# Mach-rasp.net
KiCad netlist of a schematic drawn in Altium Designer
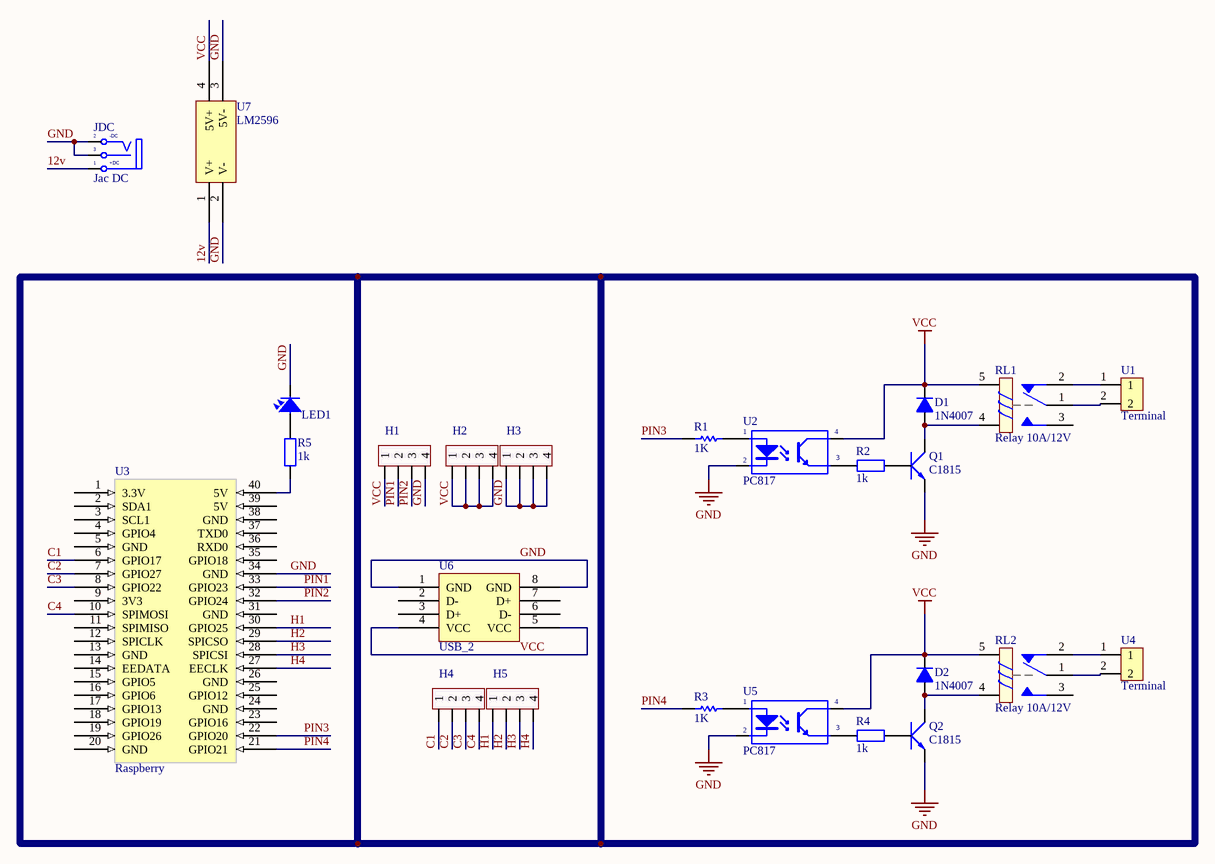
[diagram p0: Mach-rasp.SchDoc]

(export (version "E")
  (design (tool "Eeschema 10.0.6"))
  (components
    (comp (ref "D1")
      (value "1N4007")
      (footprint "D1A")
      (description "Diode 1A")
      (libsource (lib "syhaunguyen") (part "D1A"))
    )
    (comp (ref "D2")
      (value "1N4007")
      (footprint "D1A")
      (description "Diode 1A")
      (libsource (lib "syhaunguyen") (part "D1A"))
    )
    (comp (ref "H1")
      (value "Header4")
      (footprint "Header4")
      (description "Header IDC, 4 x 1 Pin Vertical 2.54mm Pitch (Non-Boxed, Male)")
      (libsource (lib "LIBRARY") (part "Header4"))
    )
    (comp (ref "H2")
      (value "Header4")
      (footprint "Header4")
      (description "Header IDC, 4 x 1 Pin Vertical 2.54mm Pitch (Non-Boxed, Male)")
      (libsource (lib "LIBRARY") (part "Header4"))
    )
    (comp (ref "H3")
      (value "Header4")
      (footprint "Header4")
      (description "Header IDC, 4 x 1 Pin Vertical 2.54mm Pitch (Non-Boxed, Male)")
      (libsource (lib "LIBRARY") (part "Header4"))
    )
    (comp (ref "H4")
      (value "Header4")
      (footprint "Header4")
      (description "Header IDC, 4 x 1 Pin Vertical 2.54mm Pitch (Non-Boxed, Male)")
      (libsource (lib "LIBRARY") (part "Header4"))
    )
    (comp (ref "H5")
      (value "Header4")
      (footprint "Header4")
      (description "Header IDC, 4 x 1 Pin Vertical 2.54mm Pitch (Non-Boxed, Male)")
      (libsource (lib "LIBRARY") (part "Header4"))
    )
    (comp (ref "JDC")
      (value "Jac DC")
      (footprint "DC-IN")
      (description "Jac DC input")
      (libsource (lib "syhaunguyen") (part "DCIN"))
    )
    (comp (ref "LED1")
      (value "LED")
      (footprint "LED-3")
      (description "LED Single colour Green and Red")
      (libsource (lib "syhaunguyen") (part "LED"))
    )
    (comp (ref "Q1")
      (value "C1815")
      (footprint "QTO-92")
      (description "NPN 600mW, ECB")
      (libsource (lib "syhaunguyen") (part "C1815"))
    )
    (comp (ref "Q2")
      (value "C1815")
      (footprint "QTO-92")
      (description "NPN 600mW, ECB")
      (libsource (lib "syhaunguyen") (part "C1815"))
    )
    (comp (ref "R1")
      (value "1K")
      (footprint "R1/4W")
      (description "Resistor")
      (fields
        (field (name "MANUFACTURER") "Generic Components")
        (field (name "Comment") "Res1")
        (field (name "PUBLISHER") "Altium Hobart Technology Centre")
      )
      (libsource (lib "syhaunguyen") (part "Res1_4"))
    )
    (comp (ref "R2")
      (value "1k")
      (footprint "R1/4W")
      (description "Resistor 1/4W")
      (libsource (lib "syhaunguyen") (part "R1/4W"))
    )
    (comp (ref "R3")
      (value "1K")
      (footprint "R1/4W")
      (description "Resistor")
      (fields
        (field (name "MANUFACTURER") "Generic Components")
        (field (name "Comment") "Res1")
        (field (name "PUBLISHER") "Altium Hobart Technology Centre")
      )
      (libsource (lib "syhaunguyen") (part "Res1_4"))
    )
    (comp (ref "R4")
      (value "1k")
      (footprint "R1/4W")
      (description "Resistor 1/4W")
      (libsource (lib "syhaunguyen") (part "R1/4W"))
    )
    (comp (ref "R5")
      (value "1k")
      (footprint "R1/4W")
      (description "Resistor 1/4W")
      (libsource (lib "syhaunguyen") (part "R1/4W"))
    )
    (comp (ref "RL1")
      (value "Relay 10A/12V")
      (footprint "RL_SPDT_10A")
      (description "Relay SPDT,10A - 12VDC 5 Pin")
      (libsource (lib "syhaunguyen") (part "Relay 1"))
    )
    (comp (ref "RL2")
      (value "Relay 10A/12V")
      (footprint "RL_SPDT_10A")
      (description "Relay SPDT,10A - 12VDC 5 Pin")
      (libsource (lib "syhaunguyen") (part "Relay 1"))
    )
    (comp (ref "U1")
      (value "Terminal")
      (footprint "Terminal 5.08")
      (libsource (lib "THU_VIEN_PQB_Schlib1") (part "TERMINAL5.08"))
    )
    (comp (ref "U2")
      (value "PC817")
      (footprint "DIP4/W0.3")
      (description "Single Opto")
      (libsource (lib "syhaunguyen") (part "PC817"))
    )
    (comp (ref "U3")
      (value "Raspberry")
      (footprint "Raspberry")
      (libsource (lib "THU_VIEN_PQB_Schlib1") (part "Raspberry"))
    )
    (comp (ref "U4")
      (value "Terminal")
      (footprint "Terminal 5.08")
      (libsource (lib "THU_VIEN_PQB_Schlib1") (part "TERMINAL5.08"))
    )
    (comp (ref "U5")
      (value "PC817")
      (footprint "DIP4/W0.3")
      (description "Single Opto")
      (libsource (lib "syhaunguyen") (part "PC817"))
    )
    (comp (ref "U6")
      (value "USB_2")
      (footprint "USB_2")
      (description "USB")
      (libsource (lib "THU_VIEN_PQB_Schlib1") (part "USB_2"))
    )
    (comp (ref "U7")
      (value "LM2596")
      (footprint "LM2596")
      (libsource (lib "THU_VIEN_PQB_Schlib1") (part "LM2596"))
    )
  )
  (nets
    (net (code "1") (name "/12v") (class "Default")
      (node (ref "JDC") (pin "1") (pinfunction "T_1") (pintype "passive"))
      (node (ref "U7") (pin "1") (pinfunction "V+_1") (pintype "power_in"))
    )
    (net (code "2") (name "/C1") (class "Default")
      (node (ref "H4") (pin "1") (pinfunction "1_1") (pintype "passive"))
      (node (ref "U3") (pin "6") (pinfunction "GPIO17_6") (pintype "input"))
    )
    (net (code "3") (name "/C2") (class "Default")
      (node (ref "H4") (pin "2") (pinfunction "2_2") (pintype "passive"))
      (node (ref "U3") (pin "7") (pinfunction "GPIO27_7") (pintype "input"))
    )
    (net (code "4") (name "/C3") (class "Default")
      (node (ref "H4") (pin "3") (pinfunction "3_3") (pintype "passive"))
      (node (ref "U3") (pin "8") (pinfunction "GPIO22_8") (pintype "input"))
    )
    (net (code "5") (name "/C4") (class "Default")
      (node (ref "H4") (pin "4") (pinfunction "4_4") (pintype "passive"))
      (node (ref "U3") (pin "10") (pinfunction "SPIMOSI_10") (pintype "input"))
    )
    (net (code "6") (name "/H1") (class "Default")
      (node (ref "H5") (pin "1") (pinfunction "1_1") (pintype "passive"))
      (node (ref "U3") (pin "30") (pinfunction "GPIO25_30") (pintype "input"))
    )
    (net (code "7") (name "/H2") (class "Default")
      (node (ref "H5") (pin "2") (pinfunction "2_2") (pintype "passive"))
      (node (ref "U3") (pin "29") (pinfunction "SPICSO_29") (pintype "input"))
    )
    (net (code "8") (name "/H3") (class "Default")
      (node (ref "H5") (pin "3") (pinfunction "3_3") (pintype "passive"))
      (node (ref "U3") (pin "28") (pinfunction "SPICSI_28") (pintype "input"))
    )
    (net (code "9") (name "/H4") (class "Default")
      (node (ref "H5") (pin "4") (pinfunction "4_4") (pintype "passive"))
      (node (ref "U3") (pin "27") (pinfunction "EECLK_27") (pintype "input"))
    )
    (net (code "10") (name "/PIN1") (class "Default")
      (node (ref "H1") (pin "2") (pinfunction "2_2") (pintype "passive"))
      (node (ref "U3") (pin "33") (pinfunction "GPIO23_33") (pintype "input"))
    )
    (net (code "11") (name "/PIN2") (class "Default")
      (node (ref "H1") (pin "3") (pinfunction "3_3") (pintype "passive"))
      (node (ref "U3") (pin "32") (pinfunction "GPIO24_32") (pintype "input"))
    )
    (net (code "12") (name "/PIN3") (class "Default")
      (node (ref "R1") (pin "2") (pinfunction "2_2") (pintype "passive"))
      (node (ref "U3") (pin "22") (pinfunction "GPIO20_22") (pintype "input"))
    )
    (net (code "13") (name "/PIN4") (class "Default")
      (node (ref "R3") (pin "2") (pinfunction "2_2") (pintype "passive"))
      (node (ref "U3") (pin "21") (pinfunction "GPIO21_21") (pintype "input"))
    )
    (net (code "14") (name "GND") (class "Default")
      (node (ref "H1") (pin "4") (pinfunction "4_4") (pintype "passive"))
      (node (ref "H3") (pin "1") (pinfunction "1_1") (pintype "passive"))
      (node (ref "H3") (pin "2") (pinfunction "2_2") (pintype "passive"))
      (node (ref "H3") (pin "3") (pinfunction "3_3") (pintype "passive"))
      (node (ref "H3") (pin "4") (pinfunction "4_4") (pintype "passive"))
      (node (ref "JDC") (pin "2") (pinfunction "TN_2") (pintype "passive"))
      (node (ref "JDC") (pin "3") (pinfunction "S_3") (pintype "power_in"))
      (node (ref "LED1") (pin "2") (pinfunction "2_2") (pintype "passive"))
      (node (ref "Q1") (pin "1") (pinfunction "E_1") (pintype "passive"))
      (node (ref "Q2") (pin "1") (pinfunction "E_1") (pintype "passive"))
      (node (ref "U2") (pin "2") (pinfunction "K_2") (pintype "passive"))
      (node (ref "U3") (pin "34") (pinfunction "GND_34") (pintype "input"))
      (node (ref "U5") (pin "2") (pinfunction "K_2") (pintype "passive"))
      (node (ref "U6") (pin "1") (pinfunction "GND_1") (pintype "passive"))
      (node (ref "U6") (pin "8") (pinfunction "GND_8") (pintype "passive"))
      (node (ref "U7") (pin "2") (pinfunction "V-_2") (pintype "power_in"))
      (node (ref "U7") (pin "3") (pinfunction "5V-_3") (pintype "power_in"))
    )
    (net (code "15") (name "Net-(D1-A)") (class "Default")
      (node (ref "D1") (pin "1") (pinfunction "A_1") (pintype "passive"))
      (node (ref "Q1") (pin "2") (pinfunction "C_2") (pintype "passive"))
      (node (ref "RL1") (pin "4") (pinfunction "4_4") (pintype "passive"))
    )
    (net (code "16") (name "Net-(D2-A)") (class "Default")
      (node (ref "D2") (pin "1") (pinfunction "A_1") (pintype "passive"))
      (node (ref "Q2") (pin "2") (pinfunction "C_2") (pintype "passive"))
      (node (ref "RL2") (pin "4") (pinfunction "4_4") (pintype "passive"))
    )
    (net (code "17") (name "Net-(LED1-Pad1)") (class "Default")
      (node (ref "LED1") (pin "1") (pinfunction "1_1") (pintype "passive"))
      (node (ref "R5") (pin "2") (pinfunction "2_2") (pintype "passive"))
    )
    (net (code "18") (name "Net-(Q1-B)") (class "Default")
      (node (ref "Q1") (pin "3") (pinfunction "B_3") (pintype "passive"))
      (node (ref "R2") (pin "2") (pinfunction "2_2") (pintype "passive"))
    )
    (net (code "19") (name "Net-(Q2-B)") (class "Default")
      (node (ref "Q2") (pin "3") (pinfunction "B_3") (pintype "passive"))
      (node (ref "R4") (pin "2") (pinfunction "2_2") (pintype "passive"))
    )
    (net (code "20") (name "Net-(R5-Pad1)") (class "Default")
      (node (ref "R5") (pin "1") (pinfunction "1_1") (pintype "passive"))
      (node (ref "U3") (pin "40") (pinfunction "5V_40") (pintype "input"))
    )
    (net (code "21") (name "Net-(RL1-Pad1)") (class "Default")
      (node (ref "RL1") (pin "1") (pinfunction "1_1") (pintype "passive"))
      (node (ref "U1") (pin "2") (pinfunction "2_2") (pintype "passive"))
    )
    (net (code "22") (name "Net-(RL1-Pad2)") (class "Default")
      (node (ref "RL1") (pin "2") (pinfunction "2_2") (pintype "passive"))
      (node (ref "U1") (pin "1") (pinfunction "1_1") (pintype "passive"))
    )
    (net (code "23") (name "Net-(RL2-Pad1)") (class "Default")
      (node (ref "RL2") (pin "1") (pinfunction "1_1") (pintype "passive"))
      (node (ref "U4") (pin "2") (pinfunction "2_2") (pintype "passive"))
    )
    (net (code "24") (name "Net-(RL2-Pad2)") (class "Default")
      (node (ref "RL2") (pin "2") (pinfunction "2_2") (pintype "passive"))
      (node (ref "U4") (pin "1") (pinfunction "1_1") (pintype "passive"))
    )
    (net (code "25") (name "Net-(U2-A)") (class "Default")
      (node (ref "R1") (pin "1") (pinfunction "1_1") (pintype "passive"))
      (node (ref "U2") (pin "1") (pinfunction "A_1") (pintype "passive"))
    )
    (net (code "26") (name "Net-(U2-E)") (class "Default")
      (node (ref "R2") (pin "1") (pinfunction "1_1") (pintype "passive"))
      (node (ref "U2") (pin "3") (pinfunction "E_3") (pintype "passive"))
    )
    (net (code "27") (name "Net-(U5-A)") (class "Default")
      (node (ref "R3") (pin "1") (pinfunction "1_1") (pintype "passive"))
      (node (ref "U5") (pin "1") (pinfunction "A_1") (pintype "passive"))
    )
    (net (code "28") (name "Net-(U5-E)") (class "Default")
      (node (ref "R4") (pin "1") (pinfunction "1_1") (pintype "passive"))
      (node (ref "U5") (pin "3") (pinfunction "E_3") (pintype "passive"))
    )
    (net (code "29") (name "VCC") (class "Default")
      (node (ref "D1") (pin "2") (pinfunction "K_2") (pintype "passive"))
      (node (ref "D2") (pin "2") (pinfunction "K_2") (pintype "passive"))
      (node (ref "H1") (pin "1") (pinfunction "1_1") (pintype "passive"))
      (node (ref "H2") (pin "1") (pinfunction "1_1") (pintype "passive"))
      (node (ref "H2") (pin "2") (pinfunction "2_2") (pintype "passive"))
      (node (ref "H2") (pin "3") (pinfunction "3_3") (pintype "passive"))
      (node (ref "H2") (pin "4") (pinfunction "4_4") (pintype "passive"))
      (node (ref "RL1") (pin "5") (pinfunction "5_5") (pintype "passive"))
      (node (ref "RL2") (pin "5") (pinfunction "5_5") (pintype "passive"))
      (node (ref "U2") (pin "4") (pinfunction "C_4") (pintype "passive"))
      (node (ref "U5") (pin "4") (pinfunction "C_4") (pintype "passive"))
      (node (ref "U6") (pin "4") (pinfunction "VCC_4") (pintype "passive"))
      (node (ref "U6") (pin "5") (pinfunction "VCC_5") (pintype "passive"))
      (node (ref "U7") (pin "4") (pinfunction "5V+_4") (pintype "power_in"))
    )
    (net (code "30") (name "unconnected-(RL1-Pad3)") (class "Default")
      (node (ref "RL1") (pin "3") (pinfunction "3_3") (pintype "passive"))
    )
    (net (code "31") (name "unconnected-(RL2-Pad3)") (class "Default")
      (node (ref "RL2") (pin "3") (pinfunction "3_3") (pintype "passive"))
    )
    (net (code "32") (name "unconnected-(U3-3.3V-Pad1)") (class "Default")
      (node (ref "U3") (pin "1") (pinfunction "3.3V_1") (pintype "input"))
    )
    (net (code "33") (name "unconnected-(U3-3V3-Pad9)") (class "Default")
      (node (ref "U3") (pin "9") (pinfunction "3V3_9") (pintype "input"))
    )
    (net (code "34") (name "unconnected-(U3-5V-Pad39)") (class "Default")
      (node (ref "U3") (pin "39") (pinfunction "5V_39") (pintype "input"))
    )
    (net (code "35") (name "unconnected-(U3-EEDATA-Pad14)") (class "Default")
      (node (ref "U3") (pin "14") (pinfunction "EEDATA_14") (pintype "input"))
    )
    (net (code "36") (name "unconnected-(U3-GND-Pad5)") (class "Default")
      (node (ref "U3") (pin "5") (pinfunction "GND_5") (pintype "input"))
    )
    (net (code "37") (name "unconnected-(U3-GND-Pad13)") (class "Default")
      (node (ref "U3") (pin "13") (pinfunction "GND_13") (pintype "input"))
    )
    (net (code "38") (name "unconnected-(U3-GND-Pad20)") (class "Default")
      (node (ref "U3") (pin "20") (pinfunction "GND_20") (pintype "input"))
    )
    (net (code "39") (name "unconnected-(U3-GND-Pad24)") (class "Default")
      (node (ref "U3") (pin "24") (pinfunction "GND_24") (pintype "input"))
    )
    (net (code "40") (name "unconnected-(U3-GND-Pad26)") (class "Default")
      (node (ref "U3") (pin "26") (pinfunction "GND_26") (pintype "input"))
    )
    (net (code "41") (name "unconnected-(U3-GND-Pad31)") (class "Default")
      (node (ref "U3") (pin "31") (pinfunction "GND_31") (pintype "input"))
    )
    (net (code "42") (name "unconnected-(U3-GND-Pad38)") (class "Default")
      (node (ref "U3") (pin "38") (pinfunction "GND_38") (pintype "input"))
    )
    (net (code "43") (name "unconnected-(U3-GPIO4-Pad4)") (class "Default")
      (node (ref "U3") (pin "4") (pinfunction "GPIO4_4") (pintype "input"))
    )
    (net (code "44") (name "unconnected-(U3-GPIO5-Pad15)") (class "Default")
      (node (ref "U3") (pin "15") (pinfunction "GPIO5_15") (pintype "input"))
    )
    (net (code "45") (name "unconnected-(U3-GPIO6-Pad16)") (class "Default")
      (node (ref "U3") (pin "16") (pinfunction "GPIO6_16") (pintype "input"))
    )
    (net (code "46") (name "unconnected-(U3-GPIO12-Pad25)") (class "Default")
      (node (ref "U3") (pin "25") (pinfunction "GPIO12_25") (pintype "input"))
    )
    (net (code "47") (name "unconnected-(U3-GPIO13-Pad17)") (class "Default")
      (node (ref "U3") (pin "17") (pinfunction "GPIO13_17") (pintype "input"))
    )
    (net (code "48") (name "unconnected-(U3-GPIO16-Pad23)") (class "Default")
      (node (ref "U3") (pin "23") (pinfunction "GPIO16_23") (pintype "input"))
    )
    (net (code "49") (name "unconnected-(U3-GPIO18-Pad35)") (class "Default")
      (node (ref "U3") (pin "35") (pinfunction "GPIO18_35") (pintype "input"))
    )
    (net (code "50") (name "unconnected-(U3-GPIO19-Pad18)") (class "Default")
      (node (ref "U3") (pin "18") (pinfunction "GPIO19_18") (pintype "input"))
    )
    (net (code "51") (name "unconnected-(U3-GPIO26-Pad19)") (class "Default")
      (node (ref "U3") (pin "19") (pinfunction "GPIO26_19") (pintype "input"))
    )
    (net (code "52") (name "unconnected-(U3-RXD0-Pad36)") (class "Default")
      (node (ref "U3") (pin "36") (pinfunction "RXD0_36") (pintype "input"))
    )
    (net (code "53") (name "unconnected-(U3-SCL1-Pad3)") (class "Default")
      (node (ref "U3") (pin "3") (pinfunction "SCL1_3") (pintype "input"))
    )
    (net (code "54") (name "unconnected-(U3-SDA1-Pad2)") (class "Default")
      (node (ref "U3") (pin "2") (pinfunction "SDA1_2") (pintype "input"))
    )
    (net (code "55") (name "unconnected-(U3-SPICLK-Pad12)") (class "Default")
      (node (ref "U3") (pin "12") (pinfunction "SPICLK_12") (pintype "input"))
    )
    (net (code "56") (name "unconnected-(U3-SPIMISO-Pad11)") (class "Default")
      (node (ref "U3") (pin "11") (pinfunction "SPIMISO_11") (pintype "input"))
    )
    (net (code "57") (name "unconnected-(U3-TXD0-Pad37)") (class "Default")
      (node (ref "U3") (pin "37") (pinfunction "TXD0_37") (pintype "input"))
    )
    (net (code "58") (name "unconnected-(U6-D+-Pad3)") (class "Default")
      (node (ref "U6") (pin "3") (pinfunction "D+_3") (pintype "passive"))
    )
    (net (code "59") (name "unconnected-(U6-D+-Pad7)") (class "Default")
      (node (ref "U6") (pin "7") (pinfunction "D+_7") (pintype "passive"))
    )
    (net (code "60") (name "unconnected-(U6-D--Pad2)") (class "Default")
      (node (ref "U6") (pin "2") (pinfunction "D-_2") (pintype "passive"))
    )
    (net (code "61") (name "unconnected-(U6-D--Pad6)") (class "Default")
      (node (ref "U6") (pin "6") (pinfunction "D-_6") (pintype "passive"))
    )
  )
)
